# flight-mag3110.net
KiCad netlist of a schematic drawn in EAGLE
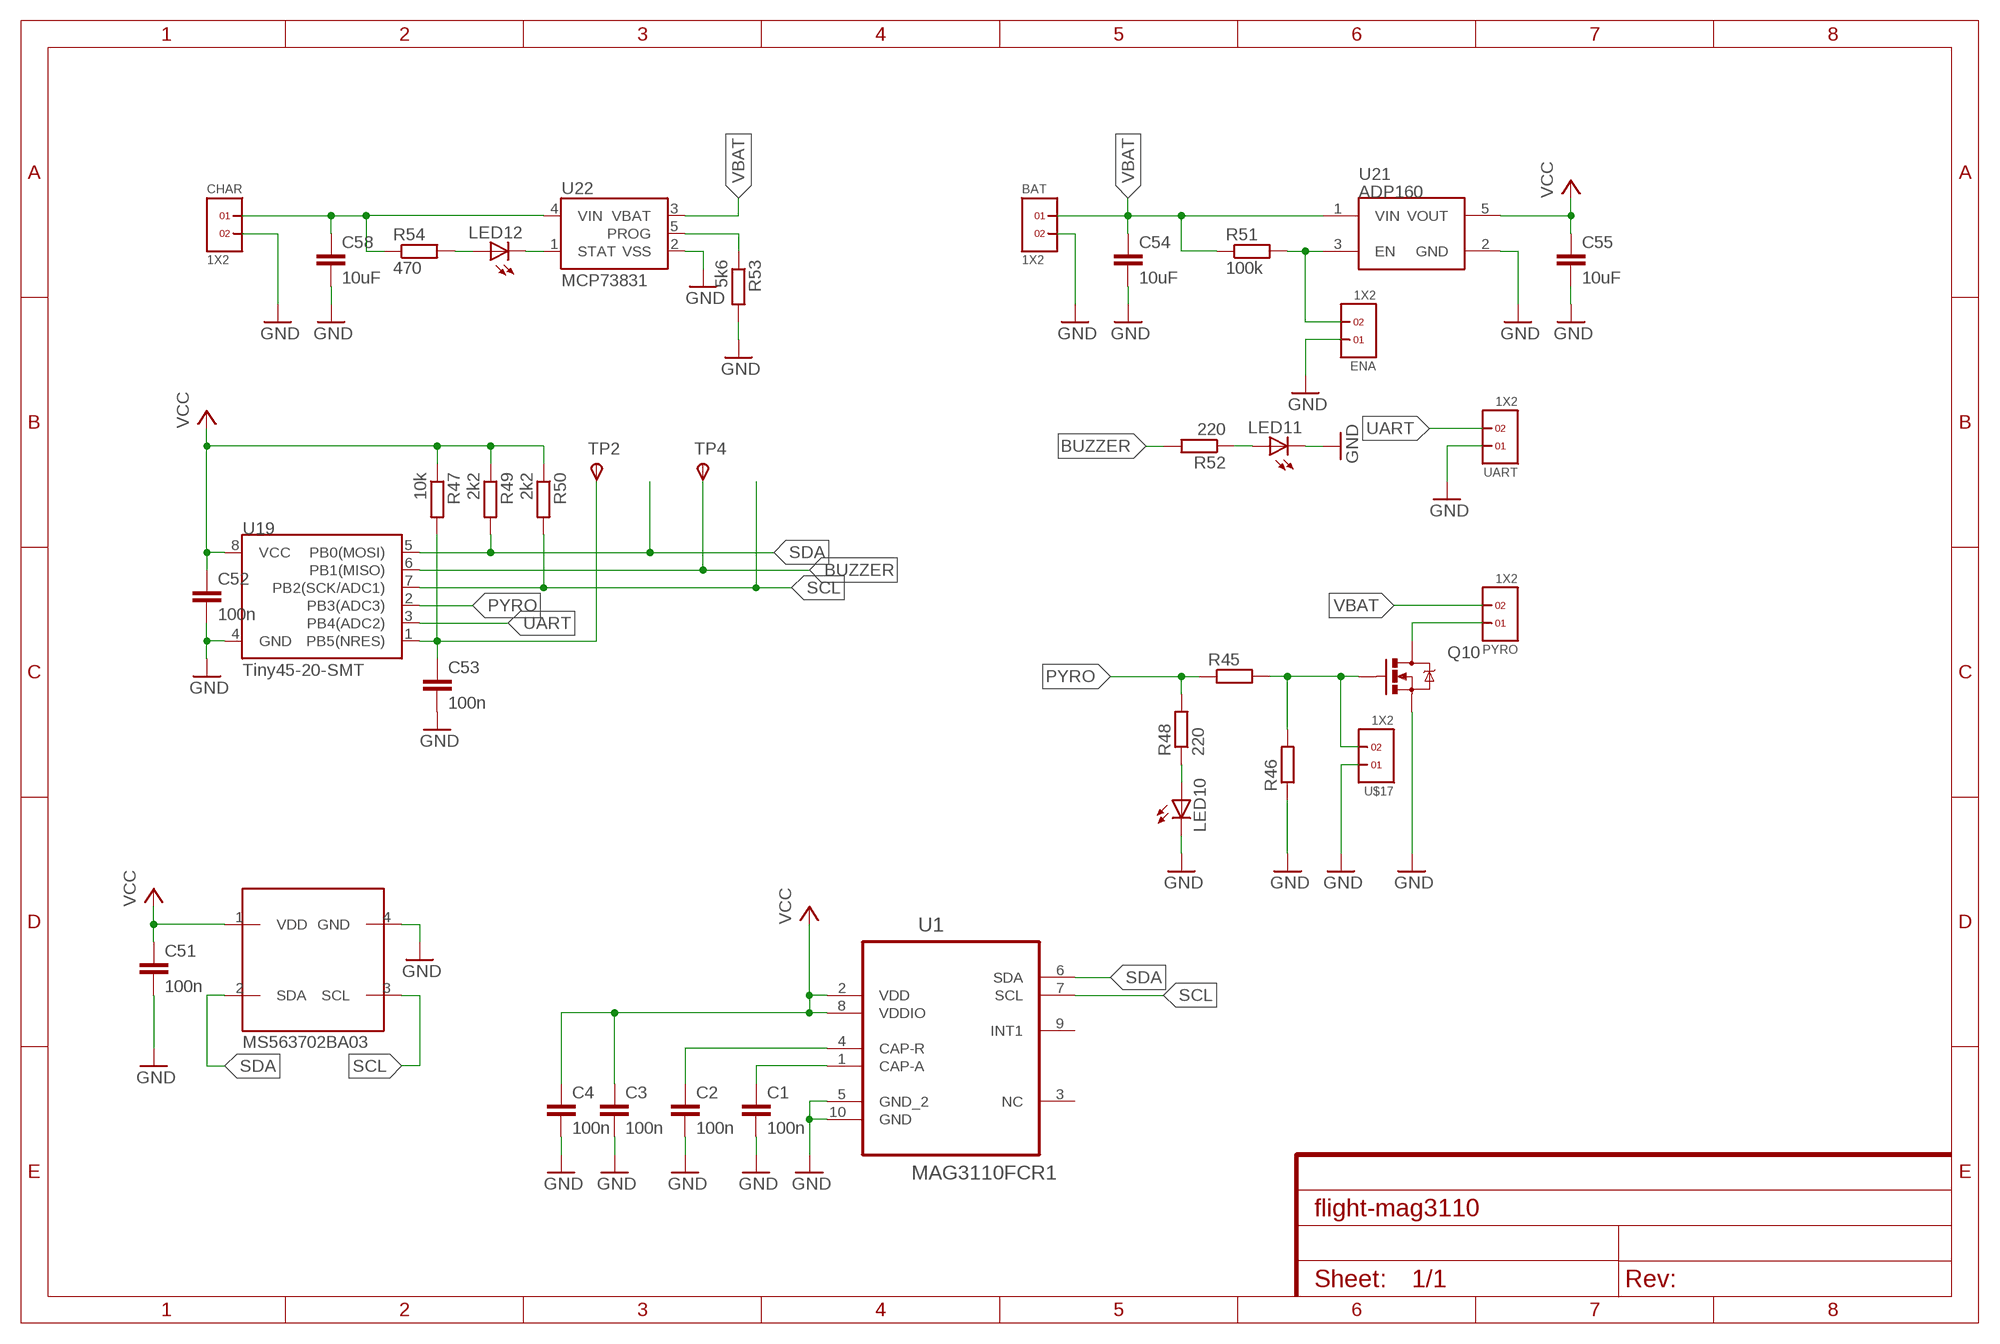
[diagram p0: schematic, sheet 1]

(export (version "E")
  (design (tool "Eeschema 10.0.6"))
  (components
    (comp (ref "BAT")
      (value "1X2")
      (footprint "eagle-import:1X2")
      (libsource (lib "eagle-import") (part "1X2"))
    )
    (comp (ref "C1")
      (value "100n")
      (footprint "eagle-import:C0603")
      (libsource (lib "eagle-import") (part "C-EUC0603"))
    )
    (comp (ref "C2")
      (value "100n")
      (footprint "eagle-import:C0603")
      (libsource (lib "eagle-import") (part "C-EUC0603"))
    )
    (comp (ref "C3")
      (value "100n")
      (footprint "eagle-import:C0603")
      (libsource (lib "eagle-import") (part "C-EUC0603"))
    )
    (comp (ref "C4")
      (value "100n")
      (footprint "eagle-import:C0603")
      (libsource (lib "eagle-import") (part "C-EUC0603"))
    )
    (comp (ref "C51")
      (value "100n")
      (footprint "eagle-import:C0603")
      (libsource (lib "eagle-import") (part "C-EUC0603"))
    )
    (comp (ref "C52")
      (value "100n")
      (footprint "eagle-import:C1206")
      (libsource (lib "eagle-import") (part "C-EUC1206"))
    )
    (comp (ref "C53")
      (value "100n")
      (footprint "eagle-import:C0603")
      (libsource (lib "eagle-import") (part "C-EUC0603"))
    )
    (comp (ref "C54")
      (value "10uF")
      (footprint "eagle-import:C0603")
      (libsource (lib "eagle-import") (part "C-EUC0603"))
    )
    (comp (ref "C55")
      (value "10uF")
      (footprint "eagle-import:C0603")
      (libsource (lib "eagle-import") (part "C-EUC0603"))
    )
    (comp (ref "C58")
      (value "10uF")
      (footprint "eagle-import:C0603")
      (libsource (lib "eagle-import") (part "C-EUC0603"))
    )
    (comp (ref "CHAR")
      (value "1X2")
      (footprint "eagle-import:1X2")
      (libsource (lib "eagle-import") (part "1X2"))
    )
    (comp (ref "ENA")
      (value "1X2")
      (footprint "eagle-import:1X2")
      (libsource (lib "eagle-import") (part "1X2"))
    )
    (comp (ref "IC2")
      (value "MS563702BA03")
      (footprint "eagle-import:MS5637")
      (libsource (lib "eagle-import") (part "MS563702BA03"))
    )
    (comp (ref "LED10")
      (value "LEDCHIPLED_0805")
      (footprint "eagle-import:CHIPLED_0805")
      (libsource (lib "eagle-import") (part "LEDCHIPLED_0805"))
    )
    (comp (ref "LED11")
      (value "LEDCHIPLED_0805")
      (footprint "eagle-import:CHIPLED_0805")
      (libsource (lib "eagle-import") (part "LEDCHIPLED_0805"))
    )
    (comp (ref "LED12")
      (value "LEDCHIPLED_0603")
      (footprint "eagle-import:CHIPLED_0603")
      (libsource (lib "eagle-import") (part "LEDCHIPLED_0603"))
    )
    (comp (ref "PYRO")
      (value "1X2")
      (footprint "eagle-import:1X2")
      (libsource (lib "eagle-import") (part "1X2"))
    )
    (comp (ref "Q10")
      (value "MOSFET-NCHANNELBSS123LT1G")
      (footprint "eagle-import:SOT23-3")
      (libsource (lib "eagle-import") (part "MOSFET-NCHANNELBSS123LT1G"))
    )
    (comp (ref "R45")
      (value "R-EU_R0603")
      (footprint "eagle-import:R0603")
      (libsource (lib "eagle-import") (part "R-EU_R0603"))
    )
    (comp (ref "R46")
      (value "R-EU_R0603")
      (footprint "eagle-import:R0603")
      (libsource (lib "eagle-import") (part "R-EU_R0603"))
    )
    (comp (ref "R47")
      (value "10k")
      (footprint "eagle-import:R0603")
      (libsource (lib "eagle-import") (part "R-EU_R0603"))
    )
    (comp (ref "R48")
      (value "220")
      (footprint "eagle-import:R0603")
      (libsource (lib "eagle-import") (part "resistor_R-EU_R0603"))
    )
    (comp (ref "R49")
      (value "2k2")
      (footprint "eagle-import:R0603")
      (libsource (lib "eagle-import") (part "R-EU_R0603"))
    )
    (comp (ref "R50")
      (value "2k2")
      (footprint "eagle-import:R0603")
      (libsource (lib "eagle-import") (part "R-EU_R0603"))
    )
    (comp (ref "R51")
      (value "100k")
      (footprint "eagle-import:R0603")
      (libsource (lib "eagle-import") (part "R-EU_R0603"))
    )
    (comp (ref "R52")
      (value "220")
      (footprint "eagle-import:R0603")
      (libsource (lib "eagle-import") (part "resistor_R-EU_R0603"))
    )
    (comp (ref "R53")
      (value "5k6")
      (footprint "eagle-import:R0603")
      (libsource (lib "eagle-import") (part "R-EU_R0603"))
    )
    (comp (ref "R54")
      (value "470")
      (footprint "eagle-import:R0603")
      (libsource (lib "eagle-import") (part "R-EU_R0603"))
    )
    (comp (ref "TP2")
      (value "TPSB1,27")
      (footprint "eagle-import:B1,27")
      (libsource (lib "eagle-import") (part "TPSB1,27"))
    )
    (comp (ref "TP4")
      (value "TPSB1,27")
      (footprint "eagle-import:B1,27")
      (libsource (lib "eagle-import") (part "TPSB1,27"))
    )
    (comp (ref "U$17")
      (value "1X2")
      (footprint "eagle-import:1X2")
      (libsource (lib "eagle-import") (part "1X2"))
    )
    (comp (ref "U1")
      (value "MAG3110FCR1")
      (footprint "eagle-import:DFN200X200X90-10N")
      (libsource (lib "eagle-import") (part "MAG3110FCR1"))
    )
    (comp (ref "U19")
      (value "Tiny45-20-SMT")
      (footprint "eagle-import:SO08-EIAJ")
      (libsource (lib "eagle-import") (part "ATTINY45TINY45-20-SMT"))
    )
    (comp (ref "U21")
      (value "ADP160")
      (footprint "eagle-import:SOT23-5")
      (libsource (lib "eagle-import") (part "ADP160"))
    )
    (comp (ref "U22")
      (value "MCP73831")
      (footprint "eagle-import:SOT23-5")
      (libsource (lib "eagle-import") (part "MCP73831"))
    )
    (comp (ref "UART")
      (value "1X2")
      (footprint "eagle-import:1X2")
      (libsource (lib "eagle-import") (part "1X2"))
    )
  )
  (nets
    (net (code "1") (name "BUZZER") (class "Default")
      (node (ref "R52") (pin "2") (pinfunction "2_2") (pintype "passive"))
      (node (ref "TP4") (pin "TP") (pinfunction "PP_TP") (pintype "input"))
      (node (ref "U19") (pin "6") (pinfunction "PB1(MISO)_6") (pintype "bidirectional"))
    )
    (net (code "2") (name "GND") (class "Default")
      (node (ref "BAT") (pin "2") (pinfunction "2_2") (pintype "bidirectional"))
      (node (ref "C1") (pin "2") (pinfunction "2_2") (pintype "passive"))
      (node (ref "C2") (pin "2") (pinfunction "2_2") (pintype "passive"))
      (node (ref "C3") (pin "2") (pinfunction "2_2") (pintype "passive"))
      (node (ref "C4") (pin "2") (pinfunction "2_2") (pintype "passive"))
      (node (ref "C51") (pin "2") (pinfunction "2_2") (pintype "passive"))
      (node (ref "C52") (pin "2") (pinfunction "2_2") (pintype "passive"))
      (node (ref "C53") (pin "2") (pinfunction "2_2") (pintype "passive"))
      (node (ref "C54") (pin "2") (pinfunction "2_2") (pintype "passive"))
      (node (ref "C55") (pin "2") (pinfunction "2_2") (pintype "passive"))
      (node (ref "C58") (pin "2") (pinfunction "2_2") (pintype "passive"))
      (node (ref "CHAR") (pin "2") (pinfunction "2_2") (pintype "bidirectional"))
      (node (ref "ENA") (pin "1") (pinfunction "1_1") (pintype "bidirectional"))
      (node (ref "IC2") (pin "4") (pinfunction "GND_4") (pintype "bidirectional"))
      (node (ref "LED10") (pin "C") (pinfunction "C_C") (pintype "passive"))
      (node (ref "LED11") (pin "C") (pinfunction "C_C") (pintype "passive"))
      (node (ref "Q10") (pin "2") (pinfunction "S_2") (pintype "passive"))
      (node (ref "R46") (pin "1") (pinfunction "1_1") (pintype "passive"))
      (node (ref "R53") (pin "2") (pinfunction "2_2") (pintype "passive"))
      (node (ref "U$17") (pin "1") (pinfunction "1_1") (pintype "bidirectional"))
      (node (ref "U1") (pin "10") (pinfunction "GND_10") (pintype "power_in"))
      (node (ref "U1") (pin "5") (pinfunction "GND_2_5") (pintype "power_in"))
      (node (ref "U19") (pin "4") (pinfunction "GND_4") (pintype "bidirectional"))
      (node (ref "U21") (pin "2") (pinfunction "GND_2") (pintype "bidirectional"))
      (node (ref "U22") (pin "2") (pinfunction "VSS_2") (pintype "power_in"))
      (node (ref "UART") (pin "1") (pinfunction "1_1") (pintype "bidirectional"))
    )
    (net (code "3") (name "Net-(LED10-PadA)") (class "Default")
      (node (ref "LED10") (pin "A") (pinfunction "A_A") (pintype "passive"))
      (node (ref "R48") (pin "1") (pinfunction "1_1") (pintype "passive"))
    )
    (net (code "4") (name "Net-(LED11-PadA)") (class "Default")
      (node (ref "LED11") (pin "A") (pinfunction "A_A") (pintype "passive"))
      (node (ref "R52") (pin "1") (pinfunction "1_1") (pintype "passive"))
    )
    (net (code "5") (name "Net-(LED12-PadA)") (class "Default")
      (node (ref "LED12") (pin "A") (pinfunction "A_A") (pintype "passive"))
      (node (ref "R54") (pin "2") (pinfunction "2_2") (pintype "passive"))
    )
    (net (code "6") (name "Net-(Q10-D)") (class "Default")
      (node (ref "PYRO") (pin "1") (pinfunction "1_1") (pintype "bidirectional"))
      (node (ref "Q10") (pin "3") (pinfunction "D_3") (pintype "passive"))
    )
    (net (code "7") (name "Net-(Q10-G)") (class "Default")
      (node (ref "Q10") (pin "1") (pinfunction "G_1") (pintype "passive"))
      (node (ref "R45") (pin "2") (pinfunction "2_2") (pintype "passive"))
      (node (ref "R46") (pin "2") (pinfunction "2_2") (pintype "passive"))
      (node (ref "U$17") (pin "2") (pinfunction "2_2") (pintype "bidirectional"))
    )
    (net (code "8") (name "Net-(TP2-PP)") (class "Default")
      (node (ref "C53") (pin "1") (pinfunction "1_1") (pintype "passive"))
      (node (ref "R47") (pin "2") (pinfunction "2_2") (pintype "passive"))
      (node (ref "TP2") (pin "TP") (pinfunction "PP_TP") (pintype "input"))
      (node (ref "U19") (pin "1") (pinfunction "PB5(NRES)_1") (pintype "bidirectional"))
    )
    (net (code "9") (name "Net-(U1-CAP-A)") (class "Default")
      (node (ref "C1") (pin "1") (pinfunction "1_1") (pintype "passive"))
      (node (ref "U1") (pin "1") (pinfunction "CAP-A_1") (pintype "passive"))
    )
    (net (code "10") (name "Net-(U1-CAP-R)") (class "Default")
      (node (ref "C2") (pin "1") (pinfunction "1_1") (pintype "passive"))
      (node (ref "U1") (pin "4") (pinfunction "CAP-R_4") (pintype "passive"))
    )
    (net (code "11") (name "Net-(U21-EN)") (class "Default")
      (node (ref "ENA") (pin "2") (pinfunction "2_2") (pintype "bidirectional"))
      (node (ref "R51") (pin "2") (pinfunction "2_2") (pintype "passive"))
      (node (ref "U21") (pin "3") (pinfunction "EN_3") (pintype "bidirectional"))
    )
    (net (code "12") (name "Net-(U22-PROG)") (class "Default")
      (node (ref "R53") (pin "1") (pinfunction "1_1") (pintype "passive"))
      (node (ref "U22") (pin "5") (pinfunction "PROG_5") (pintype "input"))
    )
    (net (code "13") (name "Net-(U22-STAT)") (class "Default")
      (node (ref "LED12") (pin "C") (pinfunction "C_C") (pintype "passive"))
      (node (ref "U22") (pin "1") (pinfunction "STAT_1") (pintype "output"))
    )
    (net (code "14") (name "Net-(U22-VIN)") (class "Default")
      (node (ref "C58") (pin "1") (pinfunction "1_1") (pintype "passive"))
      (node (ref "CHAR") (pin "1") (pinfunction "1_1") (pintype "bidirectional"))
      (node (ref "R54") (pin "1") (pinfunction "1_1") (pintype "passive"))
      (node (ref "U22") (pin "4") (pinfunction "VIN_4") (pintype "power_in"))
    )
    (net (code "15") (name "PYRO") (class "Default")
      (node (ref "R45") (pin "1") (pinfunction "1_1") (pintype "passive"))
      (node (ref "R48") (pin "2") (pinfunction "2_2") (pintype "passive"))
      (node (ref "U19") (pin "2") (pinfunction "PB3(ADC3)_2") (pintype "bidirectional"))
    )
    (net (code "16") (name "SCL") (class "Default")
      (node (ref "IC2") (pin "3") (pinfunction "SCL_3") (pintype "bidirectional"))
      (node (ref "R50") (pin "2") (pinfunction "2_2") (pintype "passive"))
      (node (ref "U1") (pin "7") (pinfunction "SCL_7") (pintype "passive"))
      (node (ref "U19") (pin "7") (pinfunction "PB2(SCK/ADC1)_7") (pintype "bidirectional"))
    )
    (net (code "17") (name "SDA") (class "Default")
      (node (ref "IC2") (pin "2") (pinfunction "SDA_2") (pintype "bidirectional"))
      (node (ref "R49") (pin "2") (pinfunction "2_2") (pintype "passive"))
      (node (ref "U1") (pin "6") (pinfunction "SDA_6") (pintype "passive"))
      (node (ref "U19") (pin "5") (pinfunction "PB0(MOSI)_5") (pintype "bidirectional"))
    )
    (net (code "18") (name "UART") (class "Default")
      (node (ref "U19") (pin "3") (pinfunction "PB4(ADC2)_3") (pintype "bidirectional"))
      (node (ref "UART") (pin "2") (pinfunction "2_2") (pintype "bidirectional"))
    )
    (net (code "19") (name "VBAT") (class "Default")
      (node (ref "BAT") (pin "1") (pinfunction "1_1") (pintype "bidirectional"))
      (node (ref "C54") (pin "1") (pinfunction "1_1") (pintype "passive"))
      (node (ref "PYRO") (pin "2") (pinfunction "2_2") (pintype "bidirectional"))
      (node (ref "R51") (pin "1") (pinfunction "1_1") (pintype "passive"))
      (node (ref "U21") (pin "1") (pinfunction "VIN_1") (pintype "bidirectional"))
      (node (ref "U22") (pin "3") (pinfunction "VBAT_3") (pintype "power_in"))
    )
    (net (code "20") (name "VCC") (class "Default")
      (node (ref "C3") (pin "1") (pinfunction "1_1") (pintype "passive"))
      (node (ref "C4") (pin "1") (pinfunction "1_1") (pintype "passive"))
      (node (ref "C51") (pin "1") (pinfunction "1_1") (pintype "passive"))
      (node (ref "C52") (pin "1") (pinfunction "1_1") (pintype "passive"))
      (node (ref "C55") (pin "1") (pinfunction "1_1") (pintype "passive"))
      (node (ref "IC2") (pin "1") (pinfunction "VDD_1") (pintype "bidirectional"))
      (node (ref "R47") (pin "1") (pinfunction "1_1") (pintype "passive"))
      (node (ref "R49") (pin "1") (pinfunction "1_1") (pintype "passive"))
      (node (ref "R50") (pin "1") (pinfunction "1_1") (pintype "passive"))
      (node (ref "U1") (pin "2") (pinfunction "VDD_2") (pintype "power_in"))
      (node (ref "U1") (pin "8") (pinfunction "VDDIO_8") (pintype "power_in"))
      (node (ref "U19") (pin "8") (pinfunction "VCC_8") (pintype "bidirectional"))
      (node (ref "U21") (pin "5") (pinfunction "VOUT_5") (pintype "bidirectional"))
    )
    (net (code "21") (name "unconnected-(U1-INT1-Pad9)") (class "Default")
      (node (ref "U1") (pin "9") (pinfunction "INT1_9") (pintype "output"))
    )
    (net (code "22") (name "unconnected-(U1-NC-Pad3)") (class "Default")
      (node (ref "U1") (pin "3") (pinfunction "NC_3") (pintype "no_connect"))
    )
  )
)
